# Cathode_Coupled_Oscillator.net
KiCad netlist of a schematic drawn in EAGLE
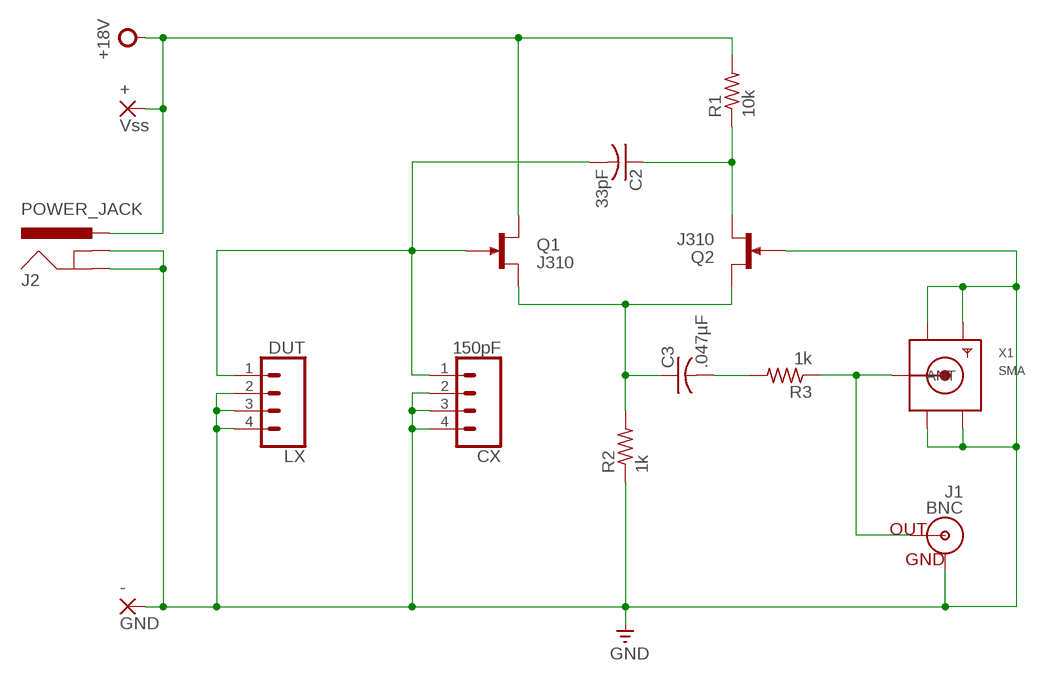
[diagram p0: schematic, sheet 1]

(export (version "E")
  (design (tool "Eeschema 10.0.6"))
  (components
    (comp (ref "+")
      (value "Vss")
      (footprint "eagle-import:2,54_1,0")
      (libsource (lib "eagle-import") (part "2,54/1,0"))
    )
    (comp (ref "-")
      (value "GND")
      (footprint "eagle-import:2,54_1,0")
      (libsource (lib "eagle-import") (part "2,54/1,0"))
    )
    (comp (ref "C2")
      (value "33pF")
      (footprint "eagle-import:C0805")
      (libsource (lib "eagle-import") (part "C-USC0805"))
    )
    (comp (ref "C3")
      (value ".047µF")
      (footprint "eagle-import:C0805")
      (libsource (lib "eagle-import") (part "C-USC0805"))
    )
    (comp (ref "CX")
      (value "150pF")
      (footprint "eagle-import:1X04")
      (libsource (lib "eagle-import") (part "CONN_04"))
    )
    (comp (ref "J1")
      (value "BNC")
      (footprint "eagle-import:BNC")
      (libsource (lib "eagle-import") (part "BNCPTH"))
    )
    (comp (ref "J2")
      (value "POWER_JACK")
      (footprint "eagle-import:POWER_JACK_PTH")
      (libsource (lib "eagle-import") (part "POWER_JACK"))
    )
    (comp (ref "LX")
      (value "DUT")
      (footprint "eagle-import:1X04")
      (libsource (lib "eagle-import") (part "CONN_04"))
    )
    (comp (ref "Q1")
      (value "J310")
      (footprint "eagle-import:SOT23")
      (libsource (lib "eagle-import") (part "MMBFJ3"))
    )
    (comp (ref "Q2")
      (value "J310")
      (footprint "eagle-import:SOT23")
      (libsource (lib "eagle-import") (part "MMBFJ3"))
    )
    (comp (ref "R1")
      (value "10k")
      (footprint "eagle-import:R0805")
      (libsource (lib "eagle-import") (part "R-US_R0805"))
    )
    (comp (ref "R2")
      (value "1k")
      (footprint "eagle-import:R0805")
      (libsource (lib "eagle-import") (part "R-US_R0805"))
    )
    (comp (ref "R3")
      (value "1k")
      (footprint "eagle-import:R0805")
      (libsource (lib "eagle-import") (part "R-US_R0805"))
    )
    (comp (ref "X1")
      (value "SMA")
      (footprint "eagle-import:SMA90_DIP")
      (libsource (lib "eagle-import") (part "SMACONNECTOR"))
    )
  )
  (nets
    (net (code "1") (name "+18V") (class "Default")
      (node (ref "+") (pin "1") (pinfunction "P_1") (pintype "passive"))
      (node (ref "J2") (pin "PWR") (pinfunction "PWR_PWR") (pintype "bidirectional"))
      (node (ref "Q1") (pin "1") (pinfunction "D_1") (pintype "passive"))
      (node (ref "R1") (pin "2") (pinfunction "2_2") (pintype "passive"))
    )
    (net (code "2") (name "GND") (class "Default")
      (node (ref "-") (pin "1") (pinfunction "P_1") (pintype "passive"))
      (node (ref "CX") (pin "2") (pinfunction "2_2") (pintype "passive"))
      (node (ref "CX") (pin "3") (pinfunction "3_3") (pintype "passive"))
      (node (ref "CX") (pin "4") (pinfunction "4_4") (pintype "passive"))
      (node (ref "J1") (pin "GND") (pinfunction "GND_GND") (pintype "bidirectional"))
      (node (ref "J2") (pin "GND") (pinfunction "GND_GND") (pintype "bidirectional"))
      (node (ref "J2") (pin "GNDBREAK") (pinfunction "GNDBREAK_GNDBREAK") (pintype "bidirectional"))
      (node (ref "LX") (pin "2") (pinfunction "2_2") (pintype "passive"))
      (node (ref "LX") (pin "3") (pinfunction "3_3") (pintype "passive"))
      (node (ref "LX") (pin "4") (pinfunction "4_4") (pintype "passive"))
      (node (ref "Q2") (pin "3") (pinfunction "G_3") (pintype "passive"))
      (node (ref "R2") (pin "1") (pinfunction "1_1") (pintype "passive"))
      (node (ref "X1") (pin "GND1") (pinfunction "GND1_GND1") (pintype "power_in"))
      (node (ref "X1") (pin "GND2") (pinfunction "GND2_GND2") (pintype "power_in"))
      (node (ref "X1") (pin "GND3") (pinfunction "GND3_GND3") (pintype "power_in"))
      (node (ref "X1") (pin "GND4") (pinfunction "GND4_GND4") (pintype "power_in"))
    )
    (net (code "3") (name "Net-(C3-Pad2)") (class "Default")
      (node (ref "C3") (pin "2") (pinfunction "2_2") (pintype "passive"))
      (node (ref "R3") (pin "2") (pinfunction "2_2") (pintype "passive"))
    )
    (net (code "4") (name "Net-(J1-OUT)") (class "Default")
      (node (ref "J1") (pin "S") (pinfunction "OUT_S") (pintype "bidirectional"))
      (node (ref "R3") (pin "1") (pinfunction "1_1") (pintype "passive"))
      (node (ref "X1") (pin "ANTENNA") (pinfunction "ANT_ANTENNA") (pintype "bidirectional"))
    )
    (net (code "5") (name "Net-(Q1-G)") (class "Default")
      (node (ref "C2") (pin "2") (pinfunction "2_2") (pintype "passive"))
      (node (ref "CX") (pin "1") (pinfunction "1_1") (pintype "passive"))
      (node (ref "LX") (pin "1") (pinfunction "1_1") (pintype "passive"))
      (node (ref "Q1") (pin "3") (pinfunction "G_3") (pintype "passive"))
    )
    (net (code "6") (name "Net-(Q1-S)") (class "Default")
      (node (ref "C3") (pin "1") (pinfunction "1_1") (pintype "passive"))
      (node (ref "Q1") (pin "2") (pinfunction "S_2") (pintype "passive"))
      (node (ref "Q2") (pin "1") (pinfunction "D_1") (pintype "passive"))
      (node (ref "R2") (pin "2") (pinfunction "2_2") (pintype "passive"))
    )
    (net (code "7") (name "Net-(Q2-S)") (class "Default")
      (node (ref "C2") (pin "1") (pinfunction "1_1") (pintype "passive"))
      (node (ref "Q2") (pin "2") (pinfunction "S_2") (pintype "passive"))
      (node (ref "R1") (pin "1") (pinfunction "1_1") (pintype "passive"))
    )
  )
)
